# selflace.net
KiCad netlist of a schematic drawn in EAGLE
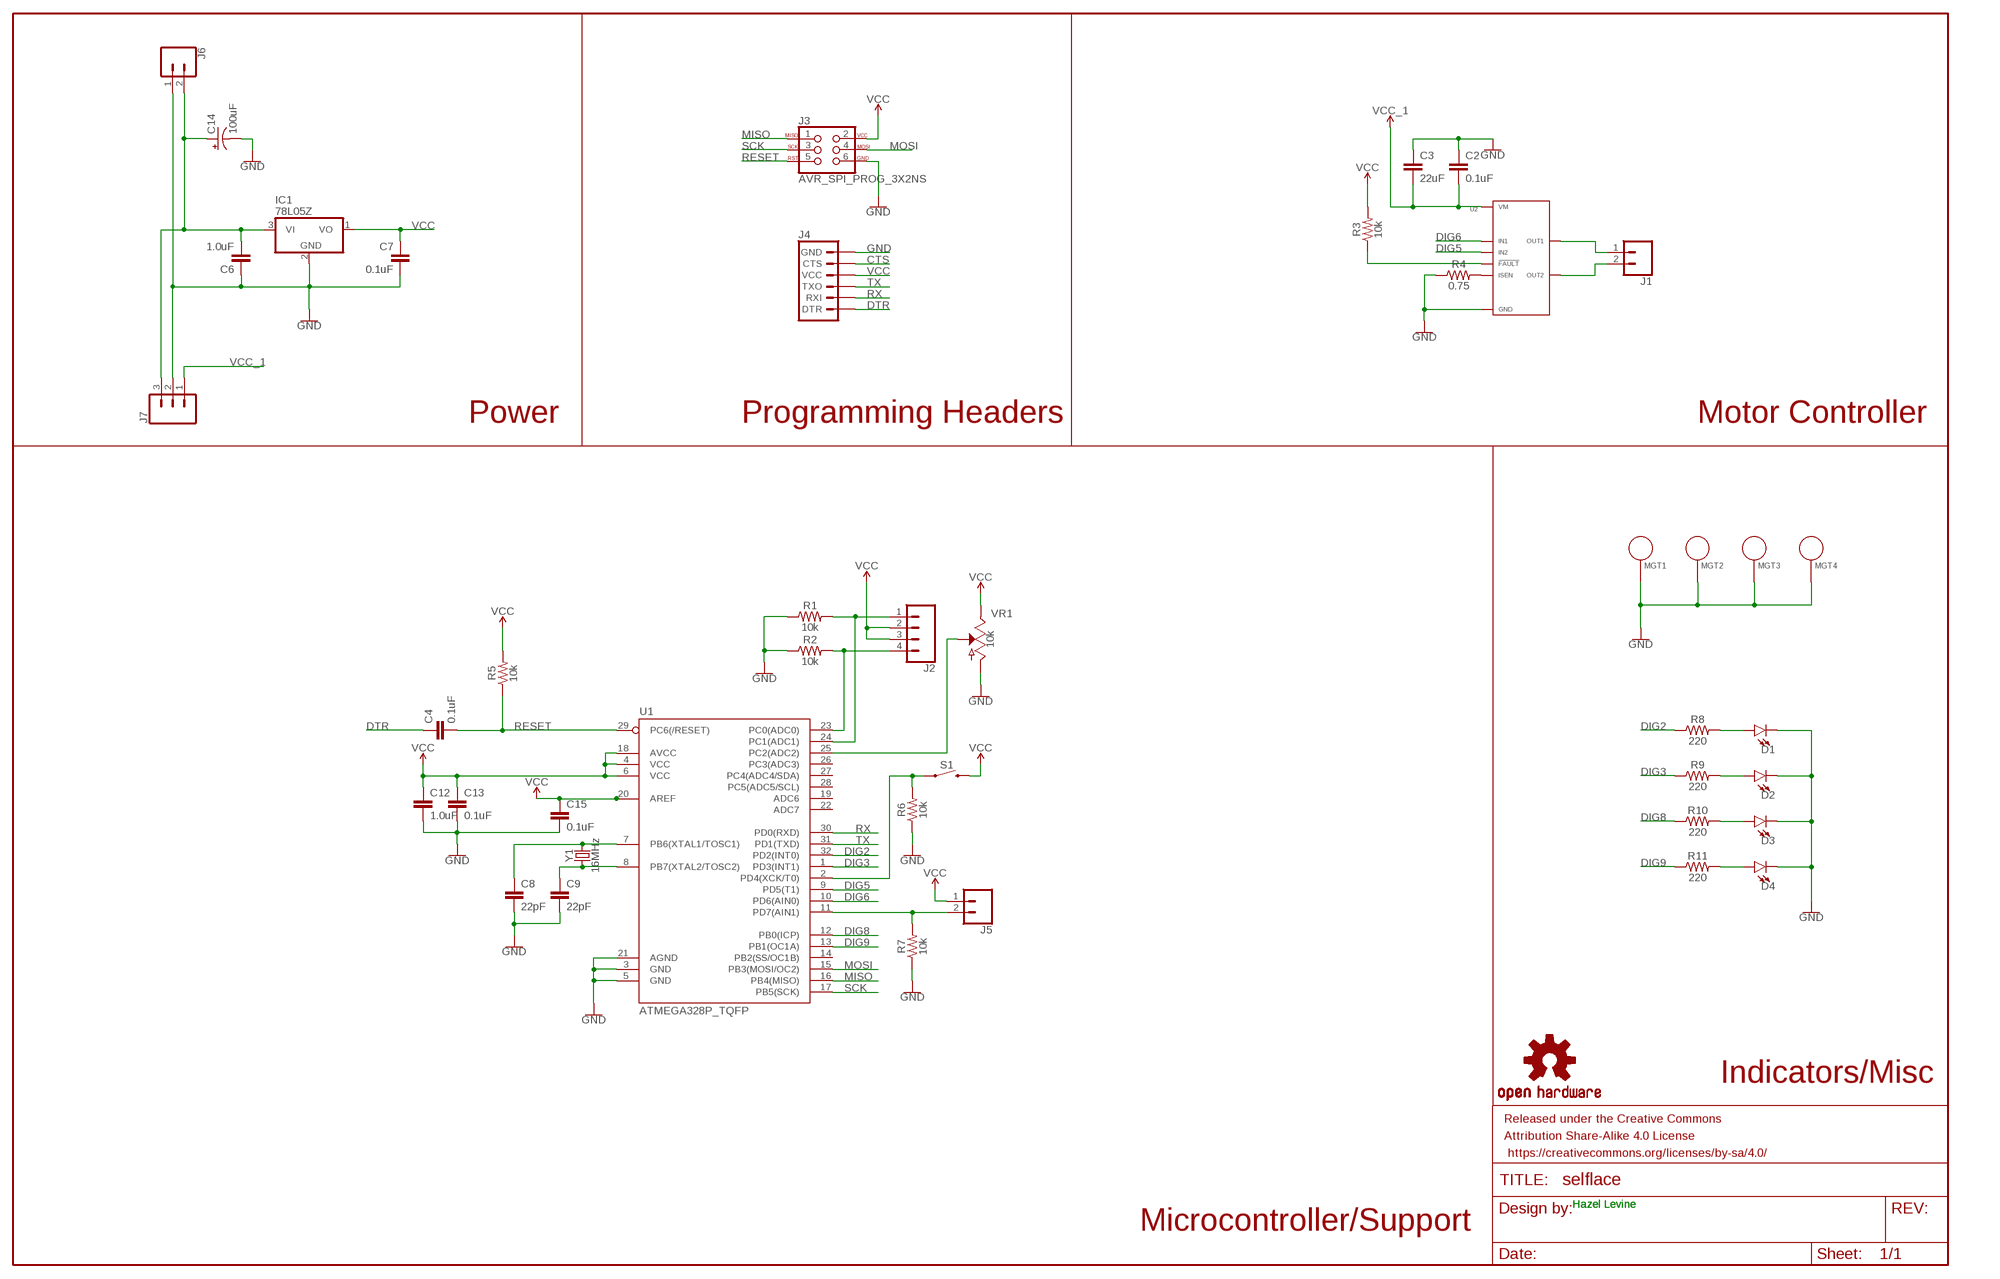
[diagram p0: schematic, sheet 1]

(export (version "E")
  (design (tool "Eeschema 10.0.6"))
  (components
    (comp (ref "C2")
      (value "0.1uF")
      (footprint "eagle-import:0603")
      (libsource (lib "eagle-import") (part "0.1UF-0603-25V-(+80/-20%)"))
    )
    (comp (ref "C3")
      (value "22uF")
      (footprint "eagle-import:0805")
      (libsource (lib "eagle-import") (part "22UF-0805-6.3V-20%"))
    )
    (comp (ref "C4")
      (value "0.1uF")
      (footprint "eagle-import:0603")
      (libsource (lib "eagle-import") (part "0.1UF-0603-25V-(+80/-20%)"))
    )
    (comp (ref "C6")
      (value "1.0uF")
      (footprint "eagle-import:0603")
      (libsource (lib "eagle-import") (part "1.0UF-0603-16V-10%"))
    )
    (comp (ref "C7")
      (value "0.1uF")
      (footprint "eagle-import:0603")
      (libsource (lib "eagle-import") (part "0.1UF-0603-25V-(+80/-20%)"))
    )
    (comp (ref "C8")
      (value "22pF")
      (footprint "eagle-import:0603")
      (libsource (lib "eagle-import") (part "22PF-0603-50V-5%"))
    )
    (comp (ref "C9")
      (value "22pF")
      (footprint "eagle-import:0603")
      (libsource (lib "eagle-import") (part "22PF-0603-50V-5%"))
    )
    (comp (ref "C12")
      (value "1.0uF")
      (footprint "eagle-import:0603")
      (libsource (lib "eagle-import") (part "1.0UF-0603-16V-10%"))
    )
    (comp (ref "C13")
      (value "0.1uF")
      (footprint "eagle-import:0603")
      (libsource (lib "eagle-import") (part "0.1UF-0603-25V-(+80/-20%)"))
    )
    (comp (ref "C14")
      (value "100uF")
      (footprint "eagle-import:NIC_10X10.5_CAP")
      (libsource (lib "eagle-import") (part "100UF-POLAR-10X10.5-63V-20%"))
    )
    (comp (ref "C15")
      (value "0.1uF")
      (footprint "eagle-import:0603")
      (libsource (lib "eagle-import") (part "0.1UF-0603-25V-(+80/-20%)"))
    )
    (comp (ref "D1")
      (value "LED1206")
      (footprint "eagle-import:LED-1206")
      (libsource (lib "eagle-import") (part "LED1206"))
    )
    (comp (ref "D2")
      (value "LED1206")
      (footprint "eagle-import:LED-1206")
      (libsource (lib "eagle-import") (part "LED1206"))
    )
    (comp (ref "D3")
      (value "LED1206")
      (footprint "eagle-import:LED-1206")
      (libsource (lib "eagle-import") (part "LED1206"))
    )
    (comp (ref "D4")
      (value "LED1206")
      (footprint "eagle-import:LED-1206")
      (libsource (lib "eagle-import") (part "LED1206"))
    )
    (comp (ref "FRAME1")
      (value "FRAME-LEDGER")
      (footprint "eagle-import:CREATIVE_COMMONS")
      (libsource (lib "eagle-import") (part "FRAME-LEDGER"))
    )
    (comp (ref "IC1")
      (value "78L05Z")
      (footprint "eagle-import:TO92")
      (libsource (lib "eagle-import") (part "78ZL05"))
    )
    (comp (ref "J1")
      (value "CONN_02")
      (footprint "eagle-import:1X02")
      (libsource (lib "eagle-import") (part "CONN_02"))
    )
    (comp (ref "J2")
      (value "CONN_04")
      (footprint "eagle-import:1X04")
      (libsource (lib "eagle-import") (part "CONN_04"))
    )
    (comp (ref "J3")
      (value "AVR_SPI_PROG_3X2NS")
      (footprint "eagle-import:2X3-NS")
      (libsource (lib "eagle-import") (part "AVR_SPI_PROG_3X2NS"))
    )
    (comp (ref "J4")
      (value "6_PIN_SERIAL_TARGETSILK")
      (footprint "eagle-import:6_PIN_SERIAL_TARGET_SIDE_W_SILK")
      (libsource (lib "eagle-import") (part "6_PIN_SERIAL_TARGETSILK"))
    )
    (comp (ref "J5")
      (value "CONN_02")
      (footprint "eagle-import:1X02")
      (libsource (lib "eagle-import") (part "CONN_02"))
    )
    (comp (ref "J6")
      (value "CONN_02JST-PTH-2")
      (footprint "eagle-import:JST-2-PTH")
      (libsource (lib "eagle-import") (part "CONN_02JST-PTH-2"))
    )
    (comp (ref "J7")
      (value "CONN_03")
      (footprint "eagle-import:1X03")
      (libsource (lib "eagle-import") (part "CONN_03"))
    )
    (comp (ref "LOGO1")
      (value "OSHW-LOGOM")
      (footprint "eagle-import:OSHW-LOGO-M")
      (libsource (lib "eagle-import") (part "OSHW-LOGOM"))
    )
    (comp (ref "MGT1")
      (value "BEAGLEBONEBLACK_MOUNTING_HOLE")
      (footprint "eagle-import:BEAGLEBONEBLACK_MOUNTING_HOLE")
      (libsource (lib "eagle-import") (part "BEAGLEBONEBLACK_MOUNTING_HOLE"))
    )
    (comp (ref "MGT2")
      (value "BEAGLEBONEBLACK_MOUNTING_HOLE")
      (footprint "eagle-import:BEAGLEBONEBLACK_MOUNTING_HOLE")
      (libsource (lib "eagle-import") (part "BEAGLEBONEBLACK_MOUNTING_HOLE"))
    )
    (comp (ref "MGT3")
      (value "BEAGLEBONEBLACK_MOUNTING_HOLE")
      (footprint "eagle-import:BEAGLEBONEBLACK_MOUNTING_HOLE")
      (libsource (lib "eagle-import") (part "BEAGLEBONEBLACK_MOUNTING_HOLE"))
    )
    (comp (ref "MGT4")
      (value "BEAGLEBONEBLACK_MOUNTING_HOLE")
      (footprint "eagle-import:BEAGLEBONEBLACK_MOUNTING_HOLE")
      (libsource (lib "eagle-import") (part "BEAGLEBONEBLACK_MOUNTING_HOLE"))
    )
    (comp (ref "R1")
      (value "10k")
      (footprint "eagle-import:0603")
      (libsource (lib "eagle-import") (part "10KOHM-0603-1/10W-1%"))
    )
    (comp (ref "R2")
      (value "10k")
      (footprint "eagle-import:0603")
      (libsource (lib "eagle-import") (part "10KOHM-0603-1/10W-1%"))
    )
    (comp (ref "R3")
      (value "10k")
      (footprint "eagle-import:0603")
      (libsource (lib "eagle-import") (part "10KOHM-0603-1/10W-1%"))
    )
    (comp (ref "R4")
      (value "0.75")
      (footprint "eagle-import:0805")
      (libsource (lib "eagle-import") (part "0.75OHM-0805-1/4W-1%"))
    )
    (comp (ref "R5")
      (value "10k")
      (footprint "eagle-import:0603")
      (libsource (lib "eagle-import") (part "10KOHM-0603-1/10W-1%"))
    )
    (comp (ref "R6")
      (value "10k")
      (footprint "eagle-import:0603")
      (libsource (lib "eagle-import") (part "10KOHM-0603-1/10W-1%"))
    )
    (comp (ref "R7")
      (value "10k")
      (footprint "eagle-import:0603")
      (libsource (lib "eagle-import") (part "10KOHM-0603-1/10W-1%"))
    )
    (comp (ref "R8")
      (value "220")
      (footprint "eagle-import:0603")
      (libsource (lib "eagle-import") (part "220OHM-0603-1/10W-1%"))
    )
    (comp (ref "R9")
      (value "220")
      (footprint "eagle-import:0603")
      (libsource (lib "eagle-import") (part "220OHM-0603-1/10W-1%"))
    )
    (comp (ref "R10")
      (value "220")
      (footprint "eagle-import:0603")
      (libsource (lib "eagle-import") (part "220OHM-0603-1/10W-1%"))
    )
    (comp (ref "R11")
      (value "220")
      (footprint "eagle-import:0603")
      (libsource (lib "eagle-import") (part "220OHM-0603-1/10W-1%"))
    )
    (comp (ref "S1")
      (value "MOMENTARY-SWITCH-SPST-PTH-6.0MM")
      (footprint "eagle-import:TACTILE_SWITCH_PTH_6.0MM")
      (libsource (lib "eagle-import") (part "MOMENTARY-SWITCH-SPST-PTH-6.0MM"))
    )
    (comp (ref "U1")
      (value "ATMEGA328P_TQFP")
      (footprint "eagle-import:TQFP32-08")
      (libsource (lib "eagle-import") (part "ATMEGA328P_TQFP"))
    )
    (comp (ref "U2")
      (value "DRV8872DDARQ1")
      (footprint "eagle-import:DRV8872_HSOP-8")
      (libsource (lib "eagle-import") (part "DRV8872DDARQ1"))
    )
    (comp (ref "VR1")
      (value "10k")
      (footprint "eagle-import:POT-PTH-ALPS")
      (libsource (lib "eagle-import") (part "POTENTIOMETER-PTH-9MM-1/20W-20%"))
    )
    (comp (ref "Y1")
      (value "16MHz")
      (footprint "eagle-import:CRYSTAL-SMD-5X3.2-4PAD")
      (libsource (lib "eagle-import") (part "CRYSTAL-16MHZSMD-5X3.2"))
    )
  )
  (nets
    (net (code "1") (name "/CTS") (class "Default")
      (node (ref "J4") (pin "P$5") (pinfunction "CTS_P$5") (pintype "passive"))
    )
    (net (code "2") (name "/DIG2") (class "Default")
      (node (ref "R8") (pin "1") (pinfunction "1_1") (pintype "passive"))
      (node (ref "U1") (pin "32") (pinfunction "PD2(INT0)_32") (pintype "bidirectional"))
    )
    (net (code "3") (name "/DIG3") (class "Default")
      (node (ref "R9") (pin "1") (pinfunction "1_1") (pintype "passive"))
      (node (ref "U1") (pin "1") (pinfunction "PD3(INT1)_1") (pintype "bidirectional"))
    )
    (net (code "4") (name "/DIG5") (class "Default")
      (node (ref "U1") (pin "9") (pinfunction "PD5(T1)_9") (pintype "bidirectional"))
      (node (ref "U2") (pin "P$2") (pinfunction "IN2_P$2") (pintype "bidirectional"))
    )
    (net (code "5") (name "/DIG6") (class "Default")
      (node (ref "U1") (pin "10") (pinfunction "PD6(AIN0)_10") (pintype "bidirectional"))
      (node (ref "U2") (pin "P$3") (pinfunction "IN1_P$3") (pintype "bidirectional"))
    )
    (net (code "6") (name "/DIG8") (class "Default")
      (node (ref "R10") (pin "1") (pinfunction "1_1") (pintype "passive"))
      (node (ref "U1") (pin "12") (pinfunction "PB0(ICP)_12") (pintype "bidirectional"))
    )
    (net (code "7") (name "/DIG9") (class "Default")
      (node (ref "R11") (pin "1") (pinfunction "1_1") (pintype "passive"))
      (node (ref "U1") (pin "13") (pinfunction "PB1(OC1A)_13") (pintype "bidirectional"))
    )
    (net (code "8") (name "/DTR") (class "Default")
      (node (ref "C4") (pin "1") (pinfunction "1_1") (pintype "passive"))
      (node (ref "J4") (pin "P$1") (pinfunction "DTR_P$1") (pintype "passive"))
    )
    (net (code "9") (name "/MISO") (class "Default")
      (node (ref "J3") (pin "1") (pinfunction "1_1") (pintype "passive"))
      (node (ref "U1") (pin "16") (pinfunction "PB4(MISO)_16") (pintype "bidirectional"))
    )
    (net (code "10") (name "/MOSI") (class "Default")
      (node (ref "J3") (pin "4") (pinfunction "4_4") (pintype "passive"))
      (node (ref "U1") (pin "15") (pinfunction "PB3(MOSI/OC2)_15") (pintype "bidirectional"))
    )
    (net (code "11") (name "/RESET") (class "Default")
      (node (ref "C4") (pin "2") (pinfunction "2_2") (pintype "passive"))
      (node (ref "J3") (pin "5") (pinfunction "5_5") (pintype "passive"))
      (node (ref "R5") (pin "1") (pinfunction "1_1") (pintype "passive"))
      (node (ref "U1") (pin "29") (pinfunction "PC6(/RESET)_29") (pintype "bidirectional"))
    )
    (net (code "12") (name "/RX") (class "Default")
      (node (ref "J4") (pin "P$3") (pinfunction "RXI_P$3") (pintype "passive"))
      (node (ref "U1") (pin "30") (pinfunction "PD0(RXD)_30") (pintype "bidirectional"))
    )
    (net (code "13") (name "/SCK") (class "Default")
      (node (ref "J3") (pin "3") (pinfunction "3_3") (pintype "passive"))
      (node (ref "U1") (pin "17") (pinfunction "PB5(SCK)_17") (pintype "bidirectional"))
    )
    (net (code "14") (name "/TX") (class "Default")
      (node (ref "J4") (pin "P$2") (pinfunction "TXO_P$2") (pintype "passive"))
      (node (ref "U1") (pin "31") (pinfunction "PD1(TXD)_31") (pintype "bidirectional"))
    )
    (net (code "15") (name "GND") (class "Default")
      (node (ref "C12") (pin "2") (pinfunction "2_2") (pintype "passive"))
      (node (ref "C13") (pin "2") (pinfunction "2_2") (pintype "passive"))
      (node (ref "C14") (pin "-") (pinfunction "-_-") (pintype "passive"))
      (node (ref "C15") (pin "2") (pinfunction "2_2") (pintype "passive"))
      (node (ref "C2") (pin "1") (pinfunction "1_1") (pintype "passive"))
      (node (ref "C3") (pin "1") (pinfunction "1_1") (pintype "passive"))
      (node (ref "C6") (pin "1") (pinfunction "1_1") (pintype "passive"))
      (node (ref "C7") (pin "2") (pinfunction "2_2") (pintype "passive"))
      (node (ref "C8") (pin "2") (pinfunction "2_2") (pintype "passive"))
      (node (ref "C9") (pin "2") (pinfunction "2_2") (pintype "passive"))
      (node (ref "D1") (pin "C") (pinfunction "C_C") (pintype "passive"))
      (node (ref "D2") (pin "C") (pinfunction "C_C") (pintype "passive"))
      (node (ref "D3") (pin "C") (pinfunction "C_C") (pintype "passive"))
      (node (ref "D4") (pin "C") (pinfunction "C_C") (pintype "passive"))
      (node (ref "IC1") (pin "2") (pinfunction "GND_2") (pintype "passive"))
      (node (ref "J3") (pin "6") (pinfunction "6_6") (pintype "passive"))
      (node (ref "J4") (pin "P$6") (pinfunction "GND_P$6") (pintype "passive"))
      (node (ref "J6") (pin "1") (pinfunction "1_1") (pintype "passive"))
      (node (ref "J7") (pin "2") (pinfunction "2_2") (pintype "passive"))
      (node (ref "MGT1") (pin "P$1") (pinfunction "P$1_P$1") (pintype "bidirectional"))
      (node (ref "MGT2") (pin "P$1") (pinfunction "P$1_P$1") (pintype "bidirectional"))
      (node (ref "MGT3") (pin "P$1") (pinfunction "P$1_P$1") (pintype "bidirectional"))
      (node (ref "MGT4") (pin "P$1") (pinfunction "P$1_P$1") (pintype "bidirectional"))
      (node (ref "R1") (pin "1") (pinfunction "1_1") (pintype "passive"))
      (node (ref "R2") (pin "1") (pinfunction "1_1") (pintype "passive"))
      (node (ref "R4") (pin "1") (pinfunction "1_1") (pintype "passive"))
      (node (ref "R6") (pin "1") (pinfunction "1_1") (pintype "passive"))
      (node (ref "R7") (pin "1") (pinfunction "1_1") (pintype "passive"))
      (node (ref "U1") (pin "21") (pinfunction "AGND_21") (pintype "bidirectional"))
      (node (ref "U1") (pin "3") (pinfunction "GND_3") (pintype "bidirectional"))
      (node (ref "U1") (pin "5") (pinfunction "GND_5") (pintype "bidirectional"))
      (node (ref "U2") (pin "P$1") (pinfunction "GND_P$1") (pintype "bidirectional"))
      (node (ref "U2") (pin "P$10") (pinfunction "GND_P$10") (pintype "bidirectional"))
      (node (ref "U2") (pin "P$11") (pinfunction "GND_P$11") (pintype "bidirectional"))
      (node (ref "U2") (pin "P$12") (pinfunction "GND_P$12") (pintype "bidirectional"))
      (node (ref "U2") (pin "P$13") (pinfunction "GND_P$13") (pintype "bidirectional"))
      (node (ref "U2") (pin "P$14") (pinfunction "GND_P$14") (pintype "bidirectional"))
      (node (ref "U2") (pin "P$15") (pinfunction "GND_P$15") (pintype "bidirectional"))
      (node (ref "U2") (pin "P$9") (pinfunction "GND_P$9") (pintype "bidirectional"))
      (node (ref "VR1") (pin "P$3") (pinfunction "A_P$3") (pintype "passive"))
    )
    (net (code "16") (name "Net-(D1-PadA)") (class "Default")
      (node (ref "D1") (pin "A") (pinfunction "A_A") (pintype "passive"))
      (node (ref "R8") (pin "2") (pinfunction "2_2") (pintype "passive"))
    )
    (net (code "17") (name "Net-(D2-PadA)") (class "Default")
      (node (ref "D2") (pin "A") (pinfunction "A_A") (pintype "passive"))
      (node (ref "R9") (pin "2") (pinfunction "2_2") (pintype "passive"))
    )
    (net (code "18") (name "Net-(D3-PadA)") (class "Default")
      (node (ref "D3") (pin "A") (pinfunction "A_A") (pintype "passive"))
      (node (ref "R10") (pin "2") (pinfunction "2_2") (pintype "passive"))
    )
    (net (code "19") (name "Net-(D4-PadA)") (class "Default")
      (node (ref "D4") (pin "A") (pinfunction "A_A") (pintype "passive"))
      (node (ref "R11") (pin "2") (pinfunction "2_2") (pintype "passive"))
    )
    (net (code "20") (name "Net-(IC1-VI)") (class "Default")
      (node (ref "C14") (pin "+") (pinfunction "+_+") (pintype "passive"))
      (node (ref "C6") (pin "2") (pinfunction "2_2") (pintype "passive"))
      (node (ref "IC1") (pin "3") (pinfunction "VI_3") (pintype "input"))
      (node (ref "J6") (pin "2") (pinfunction "2_2") (pintype "passive"))
      (node (ref "J7") (pin "3") (pinfunction "3_3") (pintype "passive"))
    )
    (net (code "21") (name "Net-(U1-PB6(XTAL1{slash}TOSC1))") (class "Default")
      (node (ref "C8") (pin "1") (pinfunction "1_1") (pintype "passive"))
      (node (ref "U1") (pin "7") (pinfunction "PB6(XTAL1/TOSC1)_7") (pintype "bidirectional"))
      (node (ref "Y1") (pin "3") (pinfunction "2_3") (pintype "passive"))
    )
    (net (code "22") (name "Net-(U1-PB7(XTAL2{slash}TOSC2))") (class "Default")
      (node (ref "C9") (pin "1") (pinfunction "1_1") (pintype "passive"))
      (node (ref "U1") (pin "8") (pinfunction "PB7(XTAL2/TOSC2)_8") (pintype "bidirectional"))
      (node (ref "Y1") (pin "1") (pinfunction "1_1") (pintype "passive"))
    )
    (net (code "23") (name "Net-(U1-PC0(ADC0))") (class "Default")
      (node (ref "J2") (pin "4") (pinfunction "4_4") (pintype "passive"))
      (node (ref "R2") (pin "2") (pinfunction "2_2") (pintype "passive"))
      (node (ref "U1") (pin "23") (pinfunction "PC0(ADC0)_23") (pintype "bidirectional"))
    )
    (net (code "24") (name "Net-(U1-PC1(ADC1))") (class "Default")
      (node (ref "J2") (pin "1") (pinfunction "1_1") (pintype "passive"))
      (node (ref "R1") (pin "2") (pinfunction "2_2") (pintype "passive"))
      (node (ref "U1") (pin "24") (pinfunction "PC1(ADC1)_24") (pintype "bidirectional"))
    )
    (net (code "25") (name "Net-(U1-PC2(ADC2))") (class "Default")
      (node (ref "U1") (pin "25") (pinfunction "PC2(ADC2)_25") (pintype "bidirectional"))
      (node (ref "VR1") (pin "P$2") (pinfunction "S_P$2") (pintype "passive"))
    )
    (net (code "26") (name "Net-(U1-PD4(XCK{slash}T0))") (class "Default")
      (node (ref "R6") (pin "2") (pinfunction "2_2") (pintype "passive"))
      (node (ref "S1") (pin "1") (pinfunction "1_1") (pintype "passive"))
      (node (ref "U1") (pin "2") (pinfunction "PD4(XCK/T0)_2") (pintype "bidirectional"))
    )
    (net (code "27") (name "Net-(U1-PD7(AIN1))") (class "Default")
      (node (ref "J5") (pin "2") (pinfunction "2_2") (pintype "passive"))
      (node (ref "R7") (pin "2") (pinfunction "2_2") (pintype "passive"))
      (node (ref "U1") (pin "11") (pinfunction "PD7(AIN1)_11") (pintype "bidirectional"))
    )
    (net (code "28") (name "Net-(U2-ISEN)") (class "Default")
      (node (ref "R4") (pin "2") (pinfunction "2_2") (pintype "passive"))
      (node (ref "U2") (pin "P$7") (pinfunction "ISEN_P$7") (pintype "bidirectional"))
    )
    (net (code "29") (name "Net-(U2-OUT1)") (class "Default")
      (node (ref "J1") (pin "1") (pinfunction "1_1") (pintype "passive"))
      (node (ref "U2") (pin "P$6") (pinfunction "OUT1_P$6") (pintype "bidirectional"))
    )
    (net (code "30") (name "Net-(U2-OUT2)") (class "Default")
      (node (ref "J1") (pin "2") (pinfunction "2_2") (pintype "passive"))
      (node (ref "U2") (pin "P$8") (pinfunction "OUT2_P$8") (pintype "bidirectional"))
    )
    (net (code "31") (name "Net-(U2-~{FAULT})") (class "Default")
      (node (ref "R3") (pin "1") (pinfunction "1_1") (pintype "passive"))
      (node (ref "U2") (pin "P$4") (pinfunction "~{FAULT}_P$4") (pintype "bidirectional"))
    )
    (net (code "32") (name "VCC") (class "Default")
      (node (ref "C12") (pin "1") (pinfunction "1_1") (pintype "passive"))
      (node (ref "C13") (pin "1") (pinfunction "1_1") (pintype "passive"))
      (node (ref "C15") (pin "1") (pinfunction "1_1") (pintype "passive"))
      (node (ref "C7") (pin "1") (pinfunction "1_1") (pintype "passive"))
      (node (ref "IC1") (pin "1") (pinfunction "VO_1") (pintype "passive"))
      (node (ref "J2") (pin "2") (pinfunction "2_2") (pintype "passive"))
      (node (ref "J2") (pin "3") (pinfunction "3_3") (pintype "passive"))
      (node (ref "J3") (pin "2") (pinfunction "2_2") (pintype "passive"))
      (node (ref "J4") (pin "P$4") (pinfunction "VCC_P$4") (pintype "passive"))
      (node (ref "J5") (pin "1") (pinfunction "1_1") (pintype "passive"))
      (node (ref "R3") (pin "2") (pinfunction "2_2") (pintype "passive"))
      (node (ref "R5") (pin "2") (pinfunction "2_2") (pintype "passive"))
      (node (ref "S1") (pin "3") (pinfunction "2_3") (pintype "passive"))
      (node (ref "U1") (pin "18") (pinfunction "AVCC_18") (pintype "bidirectional"))
      (node (ref "U1") (pin "20") (pinfunction "AREF_20") (pintype "bidirectional"))
      (node (ref "U1") (pin "4") (pinfunction "VCC_4") (pintype "bidirectional"))
      (node (ref "U1") (pin "6") (pinfunction "VCC_6") (pintype "bidirectional"))
      (node (ref "VR1") (pin "P$1") (pinfunction "E_P$1") (pintype "passive"))
    )
    (net (code "33") (name "VCC_1") (class "Default")
      (node (ref "C2") (pin "2") (pinfunction "2_2") (pintype "passive"))
      (node (ref "C3") (pin "2") (pinfunction "2_2") (pintype "passive"))
      (node (ref "J7") (pin "1") (pinfunction "1_1") (pintype "passive"))
      (node (ref "U2") (pin "P$5") (pinfunction "VM_P$5") (pintype "bidirectional"))
    )
    (net (code "34") (name "unconnected-(U1-ADC6-Pad19)") (class "Default")
      (node (ref "U1") (pin "19") (pinfunction "ADC6_19") (pintype "bidirectional"))
    )
    (net (code "35") (name "unconnected-(U1-ADC7-Pad22)") (class "Default")
      (node (ref "U1") (pin "22") (pinfunction "ADC7_22") (pintype "bidirectional"))
    )
    (net (code "36") (name "unconnected-(U1-PB2(SS{slash}OC1B)-Pad14)") (class "Default")
      (node (ref "U1") (pin "14") (pinfunction "PB2(SS/OC1B)_14") (pintype "bidirectional"))
    )
    (net (code "37") (name "unconnected-(U1-PC3(ADC3)-Pad26)") (class "Default")
      (node (ref "U1") (pin "26") (pinfunction "PC3(ADC3)_26") (pintype "bidirectional"))
    )
    (net (code "38") (name "unconnected-(U1-PC4(ADC4{slash}SDA)-Pad27)") (class "Default")
      (node (ref "U1") (pin "27") (pinfunction "PC4(ADC4/SDA)_27") (pintype "bidirectional"))
    )
    (net (code "39") (name "unconnected-(U1-PC5(ADC5{slash}SCL)-Pad28)") (class "Default")
      (node (ref "U1") (pin "28") (pinfunction "PC5(ADC5/SCL)_28") (pintype "bidirectional"))
    )
  )
)
